# Thermostat.net
KiCad netlist of a schematic drawn in EAGLE
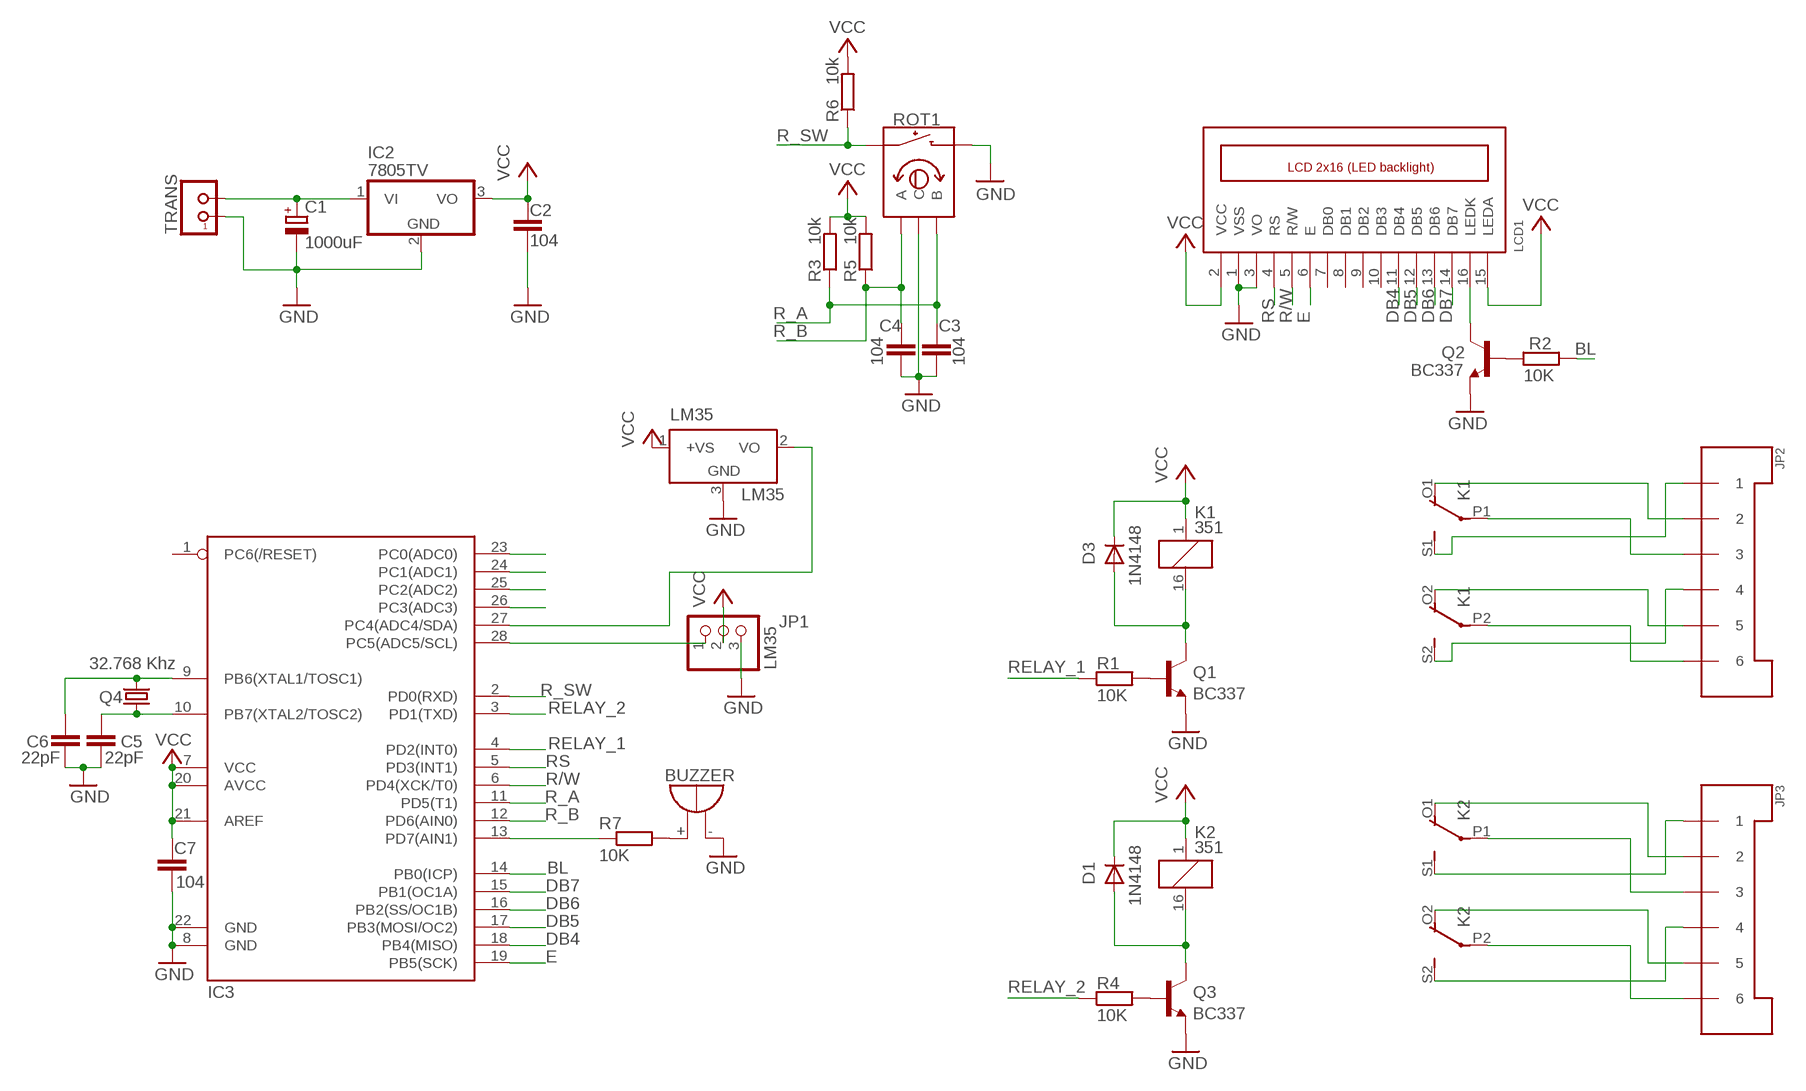
[diagram p0: schematic, sheet 1]

(export (version "E")
  (design (tool "Eeschema 10.0.6"))
  (components
    (comp (ref "BUZZER")
      (value "F/HMB")
      (footprint "eagle-import:F_HMB")
      (libsource (lib "eagle-import") (part "F/HMB"))
    )
    (comp (ref "C1")
      (value "1000uF")
      (footprint "eagle-import:C-TT2D13-SIDE")
      (libsource (lib "eagle-import") (part "C-POL13-SIDE"))
    )
    (comp (ref "C2")
      (value "104")
      (footprint "eagle-import:C-22X6(FAKI)")
      (libsource (lib "eagle-import") (part "CC-22X6(FAKI)"))
    )
    (comp (ref "C3")
      (value "104")
      (footprint "eagle-import:C-22X6(FAKI)")
      (libsource (lib "eagle-import") (part "CC-22X6(FAKI)"))
    )
    (comp (ref "C4")
      (value "104")
      (footprint "eagle-import:C-22X6(FAKI)")
      (libsource (lib "eagle-import") (part "CC-22X6(FAKI)"))
    )
    (comp (ref "C5")
      (value "22pF")
      (footprint "eagle-import:C-22X6(FAKI)")
      (libsource (lib "eagle-import") (part "CC-22X6(FAKI)"))
    )
    (comp (ref "C6")
      (value "22pF")
      (footprint "eagle-import:C-22X6(FAKI)")
      (libsource (lib "eagle-import") (part "CC-22X6(FAKI)"))
    )
    (comp (ref "C7")
      (value "104")
      (footprint "eagle-import:C-22X6(FAKI)")
      (libsource (lib "eagle-import") (part "CC-22X6(FAKI)"))
    )
    (comp (ref "D1")
      (value "1N4148")
      (footprint "eagle-import:DO35-10")
      (libsource (lib "eagle-import") (part "1N4148DO35-10"))
    )
    (comp (ref "D3")
      (value "1N4148")
      (footprint "eagle-import:DO35-10")
      (libsource (lib "eagle-import") (part "1N4148DO35-10"))
    )
    (comp (ref "IC2")
      (value "7805TV")
      (footprint "eagle-import:TO220V")
      (libsource (lib "eagle-import") (part "78TV05"))
    )
    (comp (ref "IC3")
      (value "ATMEGA-8-P")
      (footprint "eagle-import:DIL28-3")
      (libsource (lib "eagle-import") (part "ATMEGA-8-P"))
    )
    (comp (ref "JP1")
      (value "LM35")
      (footprint "eagle-import:1X03")
      (libsource (lib "eagle-import") (part "PINHD-1X3"))
    )
    (comp (ref "JP2")
      (value "KLEMES_DELMAC_6")
      (footprint "eagle-import:KLEMES_DELMAC_6")
      (libsource (lib "eagle-import") (part "KLEMES_DELMAC_6"))
    )
    (comp (ref "JP3")
      (value "KLEMES_DELMAC_6")
      (footprint "eagle-import:KLEMES_DELMAC_6")
      (libsource (lib "eagle-import") (part "KLEMES_DELMAC_6"))
    )
    (comp (ref "K1")
      (value "351")
      (footprint "eagle-import:351")
      (libsource (lib "eagle-import") (part "351"))
    )
    (comp (ref "K2")
      (value "351")
      (footprint "eagle-import:351")
      (libsource (lib "eagle-import") (part "351"))
    )
    (comp (ref "LCD1")
      (value "LCD-HD44780PINHEAD")
      (footprint "eagle-import:HD44780-2X16-PINHEAD")
      (libsource (lib "eagle-import") (part "LCD-HD44780PINHEAD"))
    )
    (comp (ref "LM35")
      (value "LM35")
      (footprint "eagle-import:TO-92")
      (libsource (lib "eagle-import") (part "LM35T0-92"))
    )
    (comp (ref "Q1")
      (value "BC337")
      (footprint "eagle-import:TO92-EBC")
      (libsource (lib "eagle-import") (part "BC548"))
    )
    (comp (ref "Q2")
      (value "BC337")
      (footprint "eagle-import:TO92-EBC")
      (libsource (lib "eagle-import") (part "BC548"))
    )
    (comp (ref "Q3")
      (value "BC337")
      (footprint "eagle-import:TO92-EBC")
      (libsource (lib "eagle-import") (part "BC548"))
    )
    (comp (ref "Q4")
      (value "32.768 Khz")
      (footprint "eagle-import:TC38")
      (libsource (lib "eagle-import") (part "CRYSTALTC38"))
    )
    (comp (ref "R1")
      (value "10K")
      (footprint "eagle-import:R0270_10")
      (libsource (lib "eagle-import") (part "R0207/10"))
    )
    (comp (ref "R2")
      (value "10K")
      (footprint "eagle-import:R0270_10")
      (libsource (lib "eagle-import") (part "R0207/10"))
    )
    (comp (ref "R3")
      (value "10k")
      (footprint "eagle-import:R0270_10")
      (libsource (lib "eagle-import") (part "R0207/10"))
    )
    (comp (ref "R4")
      (value "10K")
      (footprint "eagle-import:R0270_10")
      (libsource (lib "eagle-import") (part "R0207/10"))
    )
    (comp (ref "R5")
      (value "10k")
      (footprint "eagle-import:R0270_10")
      (libsource (lib "eagle-import") (part "R0207/10"))
    )
    (comp (ref "R6")
      (value "10k")
      (footprint "eagle-import:R0270_10")
      (libsource (lib "eagle-import") (part "R0207/10"))
    )
    (comp (ref "R7")
      (value "10K")
      (footprint "eagle-import:R0270_10")
      (libsource (lib "eagle-import") (part "R0207/10"))
    )
    (comp (ref "ROT1")
      (value "ROTARY/5-PIN")
      (footprint "eagle-import:5-PIN_RP")
      (libsource (lib "eagle-import") (part "ROTARY/5-PIN"))
    )
    (comp (ref "TRANS")
      (value "KLEMESX2")
      (footprint "eagle-import:KLEMESX2")
      (libsource (lib "eagle-import") (part "KLEMESX2"))
    )
  )
  (nets
    (net (code "1") (name "/BL") (class "Default")
      (node (ref "IC3") (pin "14") (pinfunction "PB0(ICP)_14") (pintype "bidirectional"))
      (node (ref "R2") (pin "2") (pinfunction "2_2") (pintype "passive"))
    )
    (net (code "2") (name "/DB4") (class "Default")
      (node (ref "IC3") (pin "18") (pinfunction "PB4(MISO)_18") (pintype "bidirectional"))
      (node (ref "LCD1") (pin "11") (pinfunction "DB4_11") (pintype "bidirectional"))
    )
    (net (code "3") (name "/DB5") (class "Default")
      (node (ref "IC3") (pin "17") (pinfunction "PB3(MOSI/OC2)_17") (pintype "bidirectional"))
      (node (ref "LCD1") (pin "12") (pinfunction "DB5_12") (pintype "bidirectional"))
    )
    (net (code "4") (name "/DB6") (class "Default")
      (node (ref "IC3") (pin "16") (pinfunction "PB2(SS/OC1B)_16") (pintype "bidirectional"))
      (node (ref "LCD1") (pin "13") (pinfunction "DB6_13") (pintype "bidirectional"))
    )
    (net (code "5") (name "/DB7") (class "Default")
      (node (ref "IC3") (pin "15") (pinfunction "PB1(OC1A)_15") (pintype "bidirectional"))
      (node (ref "LCD1") (pin "14") (pinfunction "DB7_14") (pintype "bidirectional"))
    )
    (net (code "6") (name "/E") (class "Default")
      (node (ref "IC3") (pin "19") (pinfunction "PB5(SCK)_19") (pintype "bidirectional"))
      (node (ref "LCD1") (pin "6") (pinfunction "E_6") (pintype "input"))
    )
    (net (code "7") (name "/RELAY_1") (class "Default")
      (node (ref "IC3") (pin "4") (pinfunction "PD2(INT0)_4") (pintype "bidirectional"))
      (node (ref "R1") (pin "1") (pinfunction "1_1") (pintype "passive"))
    )
    (net (code "8") (name "/RELAY_2") (class "Default")
      (node (ref "IC3") (pin "3") (pinfunction "PD1(TXD)_3") (pintype "bidirectional"))
      (node (ref "R4") (pin "1") (pinfunction "1_1") (pintype "passive"))
    )
    (net (code "9") (name "/RS") (class "Default")
      (node (ref "IC3") (pin "5") (pinfunction "PD3(INT1)_5") (pintype "bidirectional"))
      (node (ref "LCD1") (pin "4") (pinfunction "RS_4") (pintype "input"))
    )
    (net (code "10") (name "/R_A") (class "Default")
      (node (ref "C3") (pin "1") (pinfunction "1_1") (pintype "passive"))
      (node (ref "IC3") (pin "11") (pinfunction "PD5(T1)_11") (pintype "bidirectional"))
      (node (ref "R3") (pin "1") (pinfunction "1_1") (pintype "passive"))
      (node (ref "ROT1") (pin "B") (pinfunction "B_B") (pintype "bidirectional"))
    )
    (net (code "11") (name "/R_B") (class "Default")
      (node (ref "C4") (pin "1") (pinfunction "1_1") (pintype "passive"))
      (node (ref "IC3") (pin "12") (pinfunction "PD6(AIN0)_12") (pintype "bidirectional"))
      (node (ref "R5") (pin "1") (pinfunction "1_1") (pintype "passive"))
      (node (ref "ROT1") (pin "A") (pinfunction "A_A") (pintype "bidirectional"))
    )
    (net (code "12") (name "/R_SW") (class "Default")
      (node (ref "IC3") (pin "2") (pinfunction "PD0(RXD)_2") (pintype "bidirectional"))
      (node (ref "R6") (pin "1") (pinfunction "1_1") (pintype "passive"))
      (node (ref "ROT1") (pin "SW1") (pinfunction "SW1_SW1") (pintype "passive"))
    )
    (net (code "13") (name "/R{slash}W") (class "Default")
      (node (ref "IC3") (pin "6") (pinfunction "PD4(XCK/T0)_6") (pintype "bidirectional"))
      (node (ref "LCD1") (pin "5") (pinfunction "R/W_5") (pintype "input"))
    )
    (net (code "14") (name "GND") (class "Default")
      (node (ref "BUZZER") (pin "-") (pinfunction "-_-") (pintype "passive"))
      (node (ref "C1") (pin "-") (pinfunction "-_-") (pintype "passive"))
      (node (ref "C2") (pin "2") (pinfunction "2_2") (pintype "passive"))
      (node (ref "C3") (pin "2") (pinfunction "2_2") (pintype "passive"))
      (node (ref "C4") (pin "2") (pinfunction "2_2") (pintype "passive"))
      (node (ref "C5") (pin "2") (pinfunction "2_2") (pintype "passive"))
      (node (ref "C6") (pin "2") (pinfunction "2_2") (pintype "passive"))
      (node (ref "C7") (pin "2") (pinfunction "2_2") (pintype "passive"))
      (node (ref "IC2") (pin "2") (pinfunction "GND_2") (pintype "passive"))
      (node (ref "IC3") (pin "22") (pinfunction "GND_22") (pintype "power_in"))
      (node (ref "IC3") (pin "8") (pinfunction "GND_8") (pintype "power_in"))
      (node (ref "JP1") (pin "3") (pinfunction "3_3") (pintype "passive"))
      (node (ref "LCD1") (pin "1") (pinfunction "VSS_1") (pintype "power_in"))
      (node (ref "LCD1") (pin "3") (pinfunction "VO_3") (pintype "input"))
      (node (ref "LM35") (pin "3") (pinfunction "GND1_3") (pintype "power_in"))
      (node (ref "Q1") (pin "E") (pinfunction "E_E") (pintype "passive"))
      (node (ref "Q2") (pin "E") (pinfunction "E_E") (pintype "passive"))
      (node (ref "Q3") (pin "E") (pinfunction "E_E") (pintype "passive"))
      (node (ref "ROT1") (pin "C") (pinfunction "C_C") (pintype "bidirectional"))
      (node (ref "ROT1") (pin "SW2") (pinfunction "SW2_SW2") (pintype "passive"))
      (node (ref "TRANS") (pin "1") (pinfunction "1_1") (pintype "passive"))
    )
    (net (code "15") (name "Net-(BUZZER-Pad+)") (class "Default")
      (node (ref "BUZZER") (pin "+") (pinfunction "+_+") (pintype "passive"))
      (node (ref "R7") (pin "2") (pinfunction "2_2") (pintype "passive"))
    )
    (net (code "16") (name "Net-(IC2-VI)") (class "Default")
      (node (ref "C1") (pin "+") (pinfunction "+_+") (pintype "passive"))
      (node (ref "IC2") (pin "1") (pinfunction "VI_1") (pintype "input"))
      (node (ref "TRANS") (pin "2") (pinfunction "2_2") (pintype "passive"))
    )
    (net (code "17") (name "Net-(IC3-PB6(XTAL1{slash}TOSC1))") (class "Default")
      (node (ref "C6") (pin "1") (pinfunction "1_1") (pintype "passive"))
      (node (ref "IC3") (pin "9") (pinfunction "PB6(XTAL1/TOSC1)_9") (pintype "bidirectional"))
      (node (ref "Q4") (pin "2") (pinfunction "2_2") (pintype "passive"))
    )
    (net (code "18") (name "Net-(IC3-PB7(XTAL2{slash}TOSC2))") (class "Default")
      (node (ref "C5") (pin "1") (pinfunction "1_1") (pintype "passive"))
      (node (ref "IC3") (pin "10") (pinfunction "PB7(XTAL2/TOSC2)_10") (pintype "bidirectional"))
      (node (ref "Q4") (pin "1") (pinfunction "1_1") (pintype "passive"))
    )
    (net (code "19") (name "Net-(IC3-PC4(ADC4{slash}SDA))") (class "Default")
      (node (ref "IC3") (pin "27") (pinfunction "PC4(ADC4/SDA)_27") (pintype "bidirectional"))
      (node (ref "LM35") (pin "2") (pinfunction "VO_2") (pintype "input"))
    )
    (net (code "20") (name "Net-(IC3-PC5(ADC5{slash}SCL))") (class "Default")
      (node (ref "IC3") (pin "28") (pinfunction "PC5(ADC5/SCL)_28") (pintype "bidirectional"))
      (node (ref "JP1") (pin "1") (pinfunction "1_1") (pintype "passive"))
    )
    (net (code "21") (name "Net-(IC3-PD7(AIN1))") (class "Default")
      (node (ref "IC3") (pin "13") (pinfunction "PD7(AIN1)_13") (pintype "bidirectional"))
      (node (ref "R7") (pin "1") (pinfunction "1_1") (pintype "passive"))
    )
    (net (code "22") (name "Net-(JP2-1)") (class "Default")
      (node (ref "JP2") (pin "P$1") (pinfunction "1_P$1") (pintype "bidirectional"))
      (node (ref "K1") (pin "S1") (pinfunction "S_S1") (pintype "passive"))
    )
    (net (code "23") (name "Net-(JP2-2)") (class "Default")
      (node (ref "JP2") (pin "P$2") (pinfunction "2_P$2") (pintype "bidirectional"))
      (node (ref "K1") (pin "O1") (pinfunction "O_O1") (pintype "passive"))
    )
    (net (code "24") (name "Net-(JP2-3)") (class "Default")
      (node (ref "JP2") (pin "P$3") (pinfunction "3_P$3") (pintype "bidirectional"))
      (node (ref "K1") (pin "P1") (pinfunction "P_P1") (pintype "passive"))
    )
    (net (code "25") (name "Net-(JP2-4)") (class "Default")
      (node (ref "JP2") (pin "P$4") (pinfunction "4_P$4") (pintype "bidirectional"))
      (node (ref "K1") (pin "S2") (pinfunction "S_S2") (pintype "passive"))
    )
    (net (code "26") (name "Net-(JP2-5)") (class "Default")
      (node (ref "JP2") (pin "P$5") (pinfunction "5_P$5") (pintype "bidirectional"))
      (node (ref "K1") (pin "O2") (pinfunction "O_O2") (pintype "passive"))
    )
    (net (code "27") (name "Net-(JP2-6)") (class "Default")
      (node (ref "JP2") (pin "P$6") (pinfunction "6_P$6") (pintype "bidirectional"))
      (node (ref "K1") (pin "P2") (pinfunction "P_P2") (pintype "passive"))
    )
    (net (code "28") (name "Net-(JP3-1)") (class "Default")
      (node (ref "JP3") (pin "P$1") (pinfunction "1_P$1") (pintype "bidirectional"))
      (node (ref "K2") (pin "S1") (pinfunction "S_S1") (pintype "passive"))
    )
    (net (code "29") (name "Net-(JP3-2)") (class "Default")
      (node (ref "JP3") (pin "P$2") (pinfunction "2_P$2") (pintype "bidirectional"))
      (node (ref "K2") (pin "O1") (pinfunction "O_O1") (pintype "passive"))
    )
    (net (code "30") (name "Net-(JP3-3)") (class "Default")
      (node (ref "JP3") (pin "P$3") (pinfunction "3_P$3") (pintype "bidirectional"))
      (node (ref "K2") (pin "P1") (pinfunction "P_P1") (pintype "passive"))
    )
    (net (code "31") (name "Net-(JP3-4)") (class "Default")
      (node (ref "JP3") (pin "P$4") (pinfunction "4_P$4") (pintype "bidirectional"))
      (node (ref "K2") (pin "S2") (pinfunction "S_S2") (pintype "passive"))
    )
    (net (code "32") (name "Net-(JP3-5)") (class "Default")
      (node (ref "JP3") (pin "P$5") (pinfunction "5_P$5") (pintype "bidirectional"))
      (node (ref "K2") (pin "O2") (pinfunction "O_O2") (pintype "passive"))
    )
    (net (code "33") (name "Net-(JP3-6)") (class "Default")
      (node (ref "JP3") (pin "P$6") (pinfunction "6_P$6") (pintype "bidirectional"))
      (node (ref "K2") (pin "P2") (pinfunction "P_P2") (pintype "passive"))
    )
    (net (code "34") (name "Net-(K1A-2)") (class "Default")
      (node (ref "D3") (pin "A") (pinfunction "A_A") (pintype "passive"))
      (node (ref "K1") (pin "16") (pinfunction "2_16") (pintype "passive"))
      (node (ref "Q1") (pin "C") (pinfunction "C_C") (pintype "passive"))
    )
    (net (code "35") (name "Net-(K2A-2)") (class "Default")
      (node (ref "D1") (pin "A") (pinfunction "A_A") (pintype "passive"))
      (node (ref "K2") (pin "16") (pinfunction "2_16") (pintype "passive"))
      (node (ref "Q3") (pin "C") (pinfunction "C_C") (pintype "passive"))
    )
    (net (code "36") (name "Net-(LCD1-LEDK)") (class "Default")
      (node (ref "LCD1") (pin "16") (pinfunction "LEDK_16") (pintype "passive"))
      (node (ref "Q2") (pin "C") (pinfunction "C_C") (pintype "passive"))
    )
    (net (code "37") (name "Net-(Q1-PadB)") (class "Default")
      (node (ref "Q1") (pin "B") (pinfunction "B_B") (pintype "passive"))
      (node (ref "R1") (pin "2") (pinfunction "2_2") (pintype "passive"))
    )
    (net (code "38") (name "Net-(Q2-PadB)") (class "Default")
      (node (ref "Q2") (pin "B") (pinfunction "B_B") (pintype "passive"))
      (node (ref "R2") (pin "1") (pinfunction "1_1") (pintype "passive"))
    )
    (net (code "39") (name "Net-(Q3-PadB)") (class "Default")
      (node (ref "Q3") (pin "B") (pinfunction "B_B") (pintype "passive"))
      (node (ref "R4") (pin "2") (pinfunction "2_2") (pintype "passive"))
    )
    (net (code "40") (name "VCC") (class "Default")
      (node (ref "C2") (pin "1") (pinfunction "1_1") (pintype "passive"))
      (node (ref "C7") (pin "1") (pinfunction "1_1") (pintype "passive"))
      (node (ref "D1") (pin "C") (pinfunction "C_C") (pintype "passive"))
      (node (ref "D3") (pin "C") (pinfunction "C_C") (pintype "passive"))
      (node (ref "IC2") (pin "3") (pinfunction "VO_3") (pintype "passive"))
      (node (ref "IC3") (pin "20") (pinfunction "AVCC_20") (pintype "power_in"))
      (node (ref "IC3") (pin "21") (pinfunction "AREF_21") (pintype "passive"))
      (node (ref "IC3") (pin "7") (pinfunction "VCC_7") (pintype "power_in"))
      (node (ref "JP1") (pin "2") (pinfunction "2_2") (pintype "passive"))
      (node (ref "K1") (pin "1") (pinfunction "1_1") (pintype "passive"))
      (node (ref "K2") (pin "1") (pinfunction "1_1") (pintype "passive"))
      (node (ref "LCD1") (pin "15") (pinfunction "LEDA_15") (pintype "passive"))
      (node (ref "LCD1") (pin "2") (pinfunction "VCC_2") (pintype "power_in"))
      (node (ref "LM35") (pin "1") (pinfunction "+VS_1") (pintype "input"))
      (node (ref "R3") (pin "2") (pinfunction "2_2") (pintype "passive"))
      (node (ref "R5") (pin "2") (pinfunction "2_2") (pintype "passive"))
      (node (ref "R6") (pin "2") (pinfunction "2_2") (pintype "passive"))
    )
    (net (code "41") (name "unconnected-(IC3-PC0(ADC0)-Pad23)") (class "Default")
      (node (ref "IC3") (pin "23") (pinfunction "PC0(ADC0)_23") (pintype "bidirectional"))
    )
    (net (code "42") (name "unconnected-(IC3-PC1(ADC1)-Pad24)") (class "Default")
      (node (ref "IC3") (pin "24") (pinfunction "PC1(ADC1)_24") (pintype "bidirectional"))
    )
    (net (code "43") (name "unconnected-(IC3-PC2(ADC2)-Pad25)") (class "Default")
      (node (ref "IC3") (pin "25") (pinfunction "PC2(ADC2)_25") (pintype "bidirectional"))
    )
    (net (code "44") (name "unconnected-(IC3-PC3(ADC3)-Pad26)") (class "Default")
      (node (ref "IC3") (pin "26") (pinfunction "PC3(ADC3)_26") (pintype "bidirectional"))
    )
    (net (code "45") (name "unconnected-(IC3-PC6({slash}RESET)-Pad1)") (class "Default")
      (node (ref "IC3") (pin "1") (pinfunction "PC6(/RESET)_1") (pintype "bidirectional"))
    )
    (net (code "46") (name "unconnected-(LCD1-DB0-Pad7)") (class "Default")
      (node (ref "LCD1") (pin "7") (pinfunction "DB0_7") (pintype "bidirectional"))
    )
    (net (code "47") (name "unconnected-(LCD1-DB1-Pad8)") (class "Default")
      (node (ref "LCD1") (pin "8") (pinfunction "DB1_8") (pintype "bidirectional"))
    )
    (net (code "48") (name "unconnected-(LCD1-DB2-Pad9)") (class "Default")
      (node (ref "LCD1") (pin "9") (pinfunction "DB2_9") (pintype "bidirectional"))
    )
    (net (code "49") (name "unconnected-(LCD1-DB3-Pad10)") (class "Default")
      (node (ref "LCD1") (pin "10") (pinfunction "DB3_10") (pintype "bidirectional"))
    )
  )
)
